# ProProject___2024-05-11.net
KiCad netlist of a schematic drawn in EasyEDA Pro
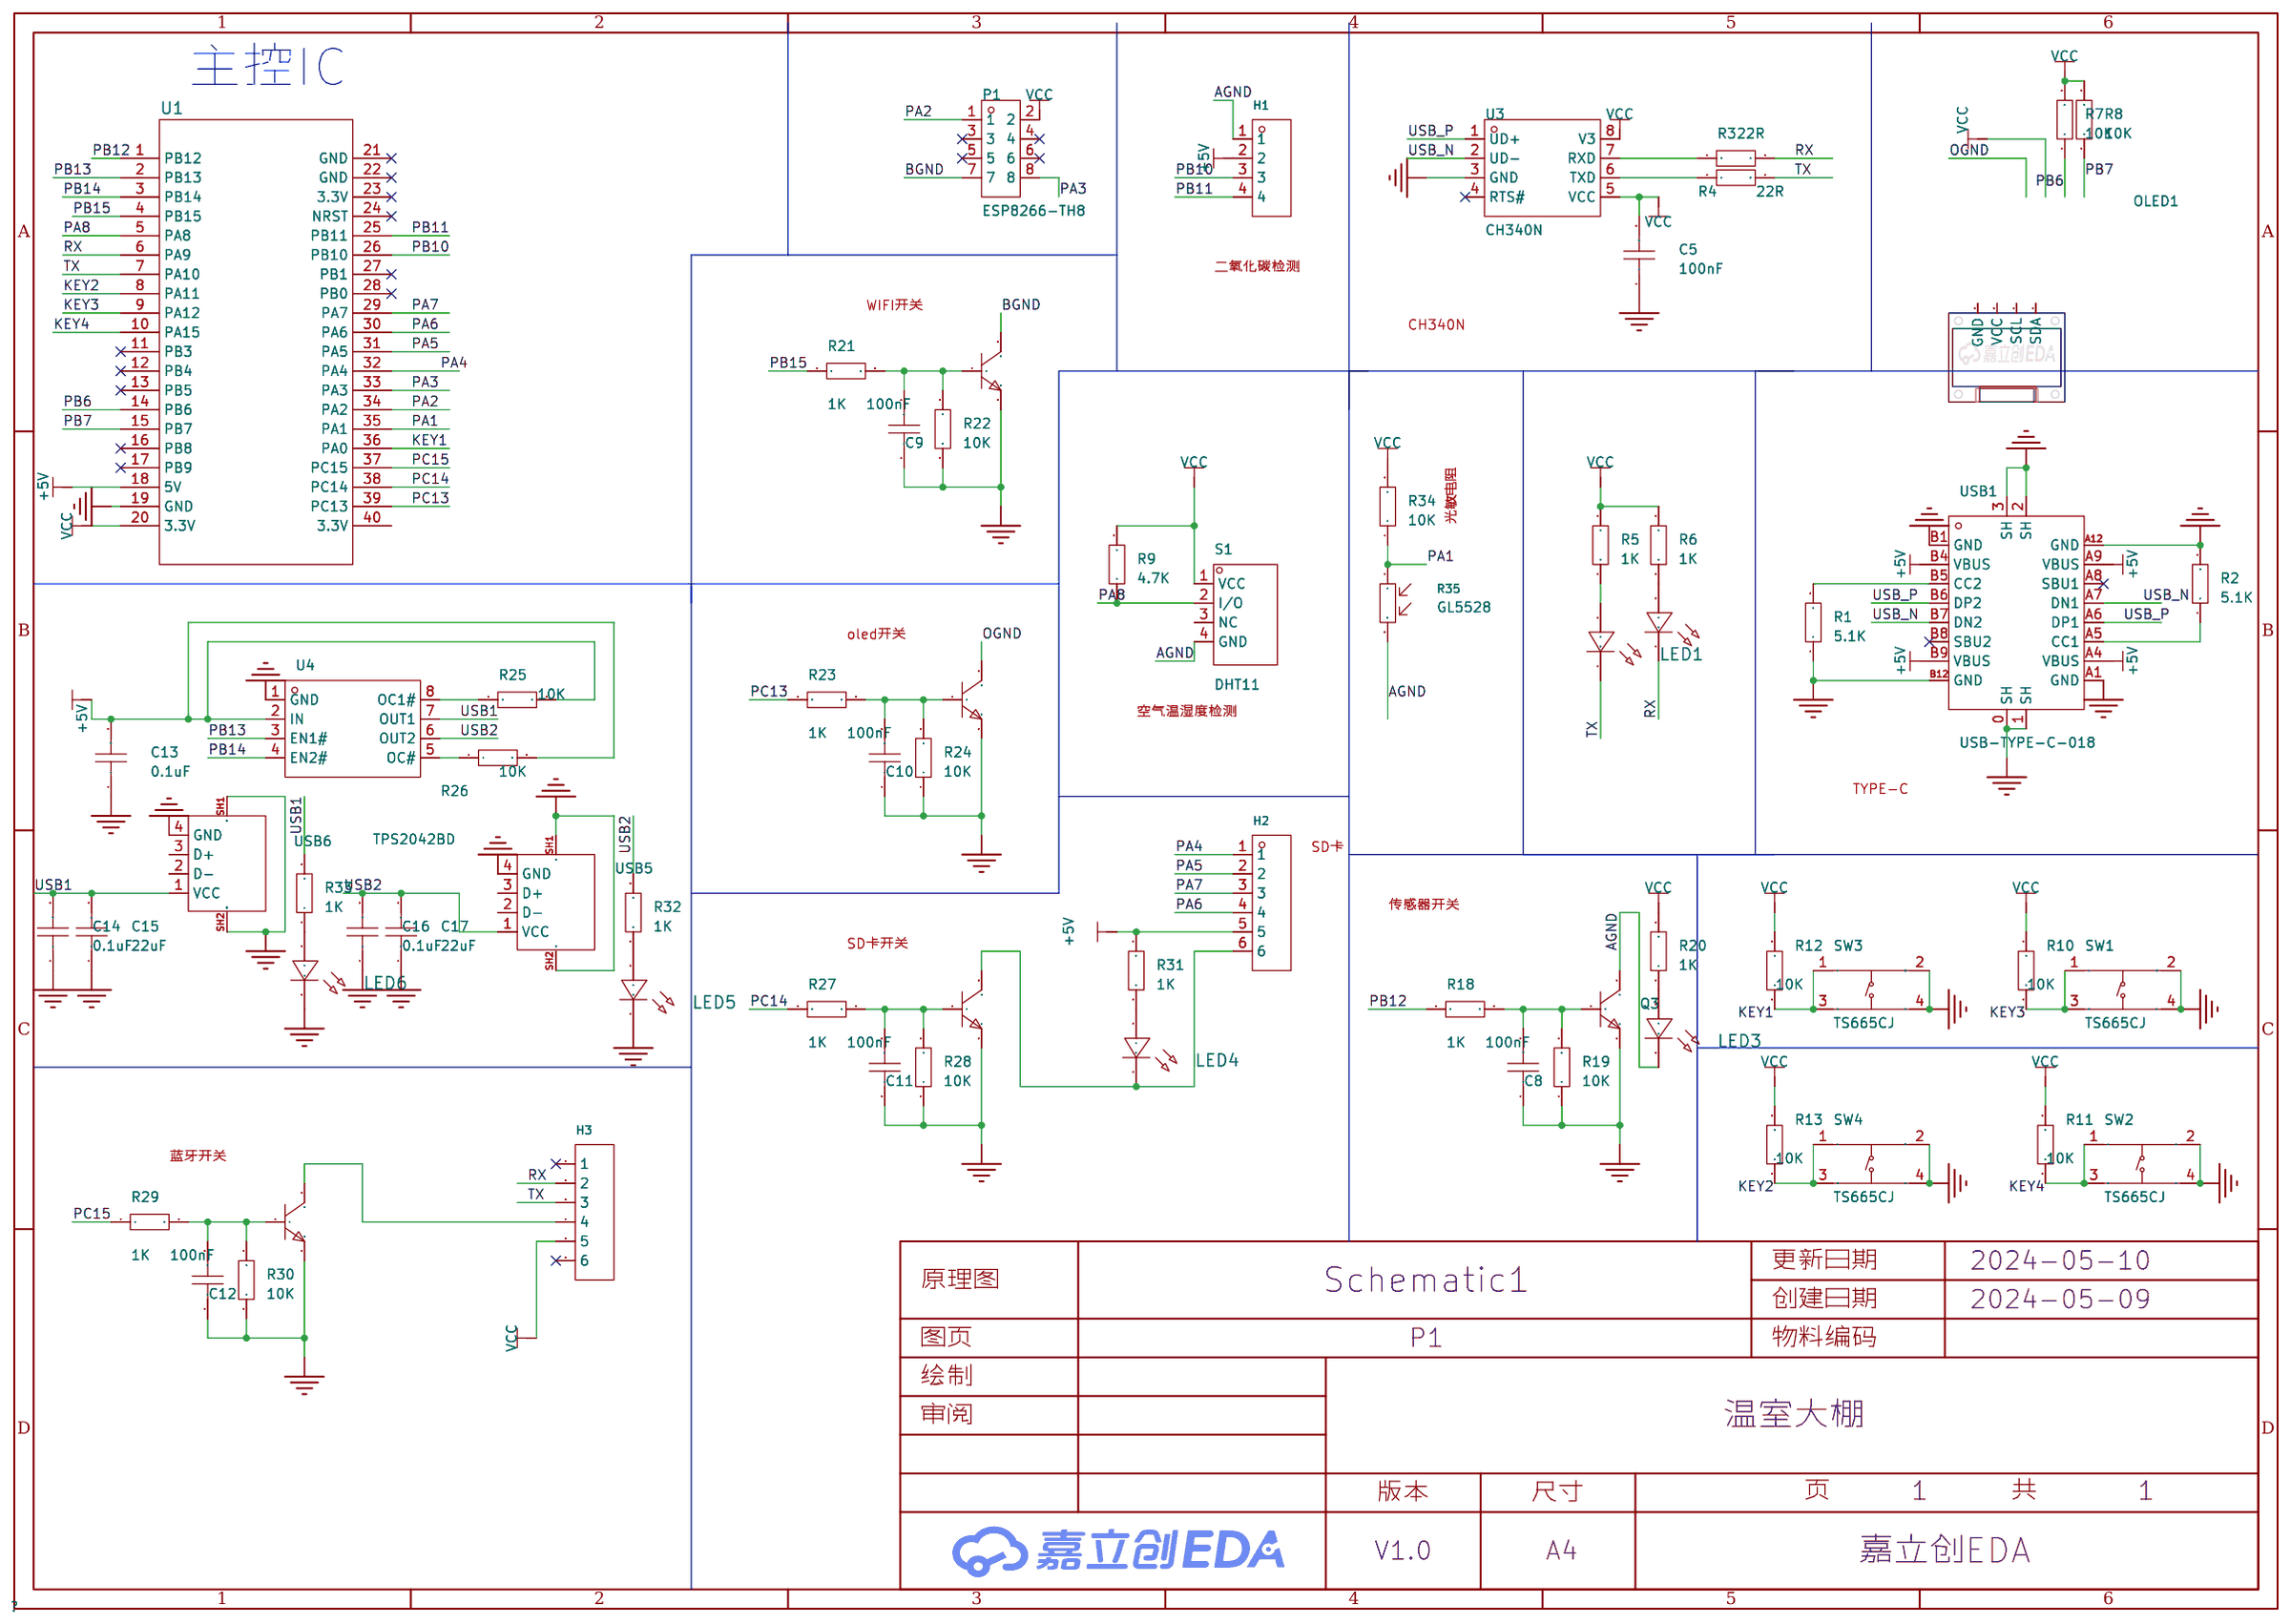
[diagram p0: schematic sheet]

(export (version "E")
  (design (tool "Eeschema 10.0.6"))
  (components
    (comp (ref "C5")
      (value "100nF")
      (footprint "easyedapro:C0603")
      (libsource (lib "easyedapro") (part "CapAcitance"))
    )
    (comp (ref "C8")
      (value "100nF")
      (footprint "easyedapro:C0603")
      (libsource (lib "easyedapro") (part "CapAcitance"))
    )
    (comp (ref "C9")
      (value "100nF")
      (footprint "easyedapro:C0603")
      (libsource (lib "easyedapro") (part "CapAcitance"))
    )
    (comp (ref "C10")
      (value "100nF")
      (footprint "easyedapro:C0603")
      (libsource (lib "easyedapro") (part "CapAcitance"))
    )
    (comp (ref "C11")
      (value "100nF")
      (footprint "easyedapro:C0603")
      (libsource (lib "easyedapro") (part "CapAcitance"))
    )
    (comp (ref "C12")
      (value "100nF")
      (footprint "easyedapro:C0603")
      (libsource (lib "easyedapro") (part "CapAcitance"))
    )
    (comp (ref "C13")
      (value "0.1uF")
      (footprint "easyedapro:C0603")
      (libsource (lib "easyedapro") (part "CapAcitance"))
    )
    (comp (ref "C14")
      (value "0.1uF")
      (footprint "easyedapro:C0603")
      (libsource (lib "easyedapro") (part "CapAcitance"))
    )
    (comp (ref "C15")
      (value "22uF")
      (footprint "easyedapro:C0603")
      (libsource (lib "easyedapro") (part "CapAcitance"))
    )
    (comp (ref "C16")
      (value "0.1uF")
      (footprint "easyedapro:C0603")
      (libsource (lib "easyedapro") (part "CapAcitance"))
    )
    (comp (ref "C17")
      (value "22uF")
      (footprint "easyedapro:C0603")
      (libsource (lib "easyedapro") (part "CapAcitance"))
    )
    (comp (ref "H1")
      (value "~")
      (footprint "easyedapro:HDR-TH_4P-P2.54-V-M")
      (libsource (lib "easyedapro") (part "PZ254V-11-04P"))
    )
    (comp (ref "H2")
      (value "~")
      (footprint "easyedapro:HDR-TH_6P-P2.54-V-F")
      (libsource (lib "easyedapro") (part "Header-Female-2.54_1x6"))
    )
    (comp (ref "H3")
      (value "~")
      (footprint "easyedapro:HDR-TH_6P-P2.54-V-M-1")
      (libsource (lib "easyedapro") (part "Header-Male-2.54_1x6"))
    )
    (comp (ref "LED1")
      (value "~")
      (footprint "easyedapro:LED_0603")
      (libsource (lib "easyedapro") (part "LED_R"))
    )
    (comp (ref "LED2")
      (value "~")
      (footprint "easyedapro:LED_0603")
      (libsource (lib "easyedapro") (part "LED_R"))
    )
    (comp (ref "LED3")
      (value "~")
      (footprint "easyedapro:LED_0603")
      (libsource (lib "easyedapro") (part "LED_R"))
    )
    (comp (ref "LED4")
      (value "~")
      (footprint "easyedapro:LED_0603")
      (libsource (lib "easyedapro") (part "LED_R"))
    )
    (comp (ref "LED5")
      (value "~")
      (footprint "easyedapro:LED_0603")
      (libsource (lib "easyedapro") (part "LED_R"))
    )
    (comp (ref "LED6")
      (value "~")
      (footprint "easyedapro:LED_0603")
      (libsource (lib "easyedapro") (part "LED_R"))
    )
    (comp (ref "OLED1")
      (value "~")
      (footprint "easyedapro:0.96OLED_4P")
      (libsource (lib "easyedapro") (part "0.96OLED模块_4P"))
    )
    (comp (ref "P1")
      (value "ESP8266-TH8")
      (footprint "easyedapro:HDR-TH_8P-P2.54-V-F-R2-C4-S2.54-1")
      (libsource (lib "easyedapro") (part "ESP8266-TH8"))
    )
    (comp (ref "Q3")
      (value "~")
      (footprint "easyedapro:S8050_SOT-23")
      (libsource (lib "easyedapro") (part "NPN"))
    )
    (comp (ref "Q4")
      (value "~")
      (footprint "easyedapro:S8050_SOT-23")
      (libsource (lib "easyedapro") (part "NPN"))
    )
    (comp (ref "Q5")
      (value "~")
      (footprint "easyedapro:S8050_SOT-23")
      (libsource (lib "easyedapro") (part "NPN"))
    )
    (comp (ref "Q6")
      (value "~")
      (footprint "easyedapro:S8050_SOT-23")
      (libsource (lib "easyedapro") (part "NPN"))
    )
    (comp (ref "Q7")
      (value "~")
      (footprint "easyedapro:S8050_SOT-23")
      (libsource (lib "easyedapro") (part "NPN"))
    )
    (comp (ref "R1") (value "5.1K") (footprint "easyedapro:R0603") (libsource (lib "easyedapro") (part "电阻")))
    (comp (ref "R2") (value "5.1K") (footprint "easyedapro:R0603") (libsource (lib "easyedapro") (part "电阻")))
    (comp (ref "R3") (value "22R") (footprint "easyedapro:R0603") (libsource (lib "easyedapro") (part "电阻")))
    (comp (ref "R4") (value "22R") (footprint "easyedapro:R0603") (libsource (lib "easyedapro") (part "电阻")))
    (comp (ref "R5") (value "1K") (footprint "easyedapro:R0603") (libsource (lib "easyedapro") (part "电阻")))
    (comp (ref "R6") (value "1K") (footprint "easyedapro:R0603") (libsource (lib "easyedapro") (part "电阻")))
    (comp (ref "R7") (value "10K") (footprint "easyedapro:R0603") (libsource (lib "easyedapro") (part "电阻")))
    (comp (ref "R8") (value "10K") (footprint "easyedapro:R0603") (libsource (lib "easyedapro") (part "电阻")))
    (comp (ref "R9") (value "4.7K") (footprint "easyedapro:R0603") (libsource (lib "easyedapro") (part "电阻")))
    (comp (ref "R10") (value "10K") (footprint "easyedapro:R0603") (libsource (lib "easyedapro") (part "电阻")))
    (comp (ref "R11") (value "10K") (footprint "easyedapro:R0603") (libsource (lib "easyedapro") (part "电阻")))
    (comp (ref "R12") (value "10K") (footprint "easyedapro:R0603") (libsource (lib "easyedapro") (part "电阻")))
    (comp (ref "R13") (value "10K") (footprint "easyedapro:R0603") (libsource (lib "easyedapro") (part "电阻")))
    (comp (ref "R18") (value "1K") (footprint "easyedapro:R0603") (libsource (lib "easyedapro") (part "电阻")))
    (comp (ref "R19") (value "10K") (footprint "easyedapro:R0603") (libsource (lib "easyedapro") (part "电阻")))
    (comp (ref "R20") (value "1K") (footprint "easyedapro:R0603") (libsource (lib "easyedapro") (part "电阻")))
    (comp (ref "R21") (value "1K") (footprint "easyedapro:R0603") (libsource (lib "easyedapro") (part "电阻")))
    (comp (ref "R22") (value "10K") (footprint "easyedapro:R0603") (libsource (lib "easyedapro") (part "电阻")))
    (comp (ref "R23") (value "1K") (footprint "easyedapro:R0603") (libsource (lib "easyedapro") (part "电阻")))
    (comp (ref "R24") (value "10K") (footprint "easyedapro:R0603") (libsource (lib "easyedapro") (part "电阻")))
    (comp (ref "R25") (value "10K") (footprint "easyedapro:R0603") (libsource (lib "easyedapro") (part "电阻")))
    (comp (ref "R26") (value "10K") (footprint "easyedapro:R0603") (libsource (lib "easyedapro") (part "电阻")))
    (comp (ref "R27") (value "1K") (footprint "easyedapro:R0603") (libsource (lib "easyedapro") (part "电阻")))
    (comp (ref "R28") (value "10K") (footprint "easyedapro:R0603") (libsource (lib "easyedapro") (part "电阻")))
    (comp (ref "R29") (value "1K") (footprint "easyedapro:R0603") (libsource (lib "easyedapro") (part "电阻")))
    (comp (ref "R30") (value "10K") (footprint "easyedapro:R0603") (libsource (lib "easyedapro") (part "电阻")))
    (comp (ref "R31") (value "1K") (footprint "easyedapro:R0603") (libsource (lib "easyedapro") (part "电阻")))
    (comp (ref "R32") (value "1K") (footprint "easyedapro:R0603") (libsource (lib "easyedapro") (part "电阻")))
    (comp (ref "R33") (value "1K") (footprint "easyedapro:R0603") (libsource (lib "easyedapro") (part "电阻")))
    (comp (ref "R34") (value "10K") (footprint "easyedapro:R0603") (libsource (lib "easyedapro") (part "电阻")))
    (comp (ref "R35")
      (value "GL5528")
      (footprint "easyedapro:RES-TH_L5.1-W4.3-P3.40-D0.5")
      (description "暗电阻:1MΩ;亮电阻 @ 10Lux:8kΩ~20kΩ;光谱峰值(波长):540nm;")
      (fields (field (name "Manufacturer") "森霸"))
      (libsource (lib "easyedapro") (part "GL5528"))
    )
    (comp (ref "S1")
      (value "DHT11")
      (footprint "easyedapro:SENSOR-TH_DHT11-1")
      (description "温湿度模块，数字式，单总线")
      (libsource (lib "easyedapro") (part "DHT11_C87032"))
    )
    (comp (ref "SW1")
      (value "TS665CJ")
      (footprint "easyedapro:SW-TH_4P-L6.0-W6.0-P4.50-LS6.5")
      (description "电路结构:单刀单掷;按钮形状:圆形按钮;安装方式:直插;开关长度:6mm;开关宽度:6mm;开关高度:5mm;触点电流:50mA;额定电压(DC):12V;带灯:-;机械寿命:-;")
      (fields (field (name "Manufacturer") "SHOU HAN(首韩)"))
      (libsource (lib "easyedapro") (part "TS665CJ"))
    )
    (comp (ref "SW2")
      (value "TS665CJ")
      (footprint "easyedapro:SW-TH_4P-L6.0-W6.0-P4.50-LS6.5")
      (description "电路结构:单刀单掷;按钮形状:圆形按钮;安装方式:直插;开关长度:6mm;开关宽度:6mm;开关高度:5mm;触点电流:50mA;额定电压(DC):12V;带灯:-;机械寿命:-;")
      (fields (field (name "Manufacturer") "SHOU HAN(首韩)"))
      (libsource (lib "easyedapro") (part "TS665CJ"))
    )
    (comp (ref "SW3")
      (value "TS665CJ")
      (footprint "easyedapro:SW-TH_4P-L6.0-W6.0-P4.50-LS6.5")
      (description "电路结构:单刀单掷;按钮形状:圆形按钮;安装方式:直插;开关长度:6mm;开关宽度:6mm;开关高度:5mm;触点电流:50mA;额定电压(DC):12V;带灯:-;机械寿命:-;")
      (fields (field (name "Manufacturer") "SHOU HAN(首韩)"))
      (libsource (lib "easyedapro") (part "TS665CJ"))
    )
    (comp (ref "SW4")
      (value "TS665CJ")
      (footprint "easyedapro:SW-TH_4P-L6.0-W6.0-P4.50-LS6.5")
      (description "电路结构:单刀单掷;按钮形状:圆形按钮;安装方式:直插;开关长度:6mm;开关宽度:6mm;开关高度:5mm;触点电流:50mA;额定电压(DC):12V;带灯:-;机械寿命:-;")
      (fields (field (name "Manufacturer") "SHOU HAN(首韩)"))
      (libsource (lib "easyedapro") (part "TS665CJ"))
    )
    (comp (ref "U1")
      (value "STM32F103C8T6最小系统")
      (footprint "easyedapro:STM32F103C8T6")
      (libsource (lib "easyedapro") (part "STM32F103C8T6最小系统_1"))
    )
    (comp (ref "U3")
      (value "CH340N")
      (footprint "easyedapro:SOP-8_L4.9-W3.9-P1.27-LS6.0-BL")
      (fields (field (name "Manufacturer") "WCH(南京沁恒)"))
      (libsource (lib "easyedapro") (part "CH340N_C2977777"))
    )
    (comp (ref "U4")
      (value "TPS2042BD")
      (footprint "easyedapro:SOIC-8_L5.0-W4.0-P1.27-LS6.1-BL")
      (description "通道数:2;输出电流:500mA;输入电压:2.7V~5.5V;导通电阻:70mΩ;")
      (fields (field (name "Manufacturer") "TI(德州仪器)"))
      (libsource (lib "easyedapro") (part "TPS2042BD"))
    )
    (comp (ref "USB1")
      (value "USB-TYPE-C-018")
      (footprint "easyedapro:USB-C_SMD-TYPE-C-31-M-12")
      (description "连接器类型:Type-C;标准:-;公母:母;端口数量:1;触点数量:16P;安装方式:卧贴;额定电流 - 电源:3A;工作温度范围:-25°C~+85°C;")
      (fields (field (name "Manufacturer") "DEALON(德艺隆)"))
      (libsource (lib "easyedapro") (part "USB-TYPE-C-018"))
    )
    (comp (ref "USB5")
      (value "~")
      (footprint "easyedapro:USB_ Type-A")
      (libsource (lib "easyedapro") (part "USB_Type-A"))
    )
    (comp (ref "USB6")
      (value "~")
      (footprint "easyedapro:USB_ Type-A")
      (libsource (lib "easyedapro") (part "USB_Type-A"))
    )
  )
  (nets
    (net (code "1") (name "+5V") (class "Default")
      (node (ref "C13") (pin "2") (pinfunction "2_2") (pintype "input"))
      (node (ref "H1") (pin "2") (pinfunction "2_2") (pintype "input"))
      (node (ref "H2") (pin "5") (pinfunction "5_5") (pintype "input"))
      (node (ref "R25") (pin "2") (pinfunction "2_2") (pintype "input"))
      (node (ref "R26") (pin "2") (pinfunction "2_2") (pintype "input"))
      (node (ref "R31") (pin "2") (pinfunction "2_2") (pintype "input"))
      (node (ref "U1") (pin "18") (pinfunction "5V_18") (pintype "input"))
      (node (ref "U4") (pin "2") (pinfunction "IN_2") (pintype "input"))
      (node (ref "USB1") (pin "A4") (pinfunction "VBUS_A4") (pintype "unspecified"))
      (node (ref "USB1") (pin "A9") (pinfunction "VBUS_A9") (pintype "unspecified"))
      (node (ref "USB1") (pin "B4") (pinfunction "VBUS_B4") (pintype "unspecified"))
      (node (ref "USB1") (pin "B9") (pinfunction "VBUS_B9") (pintype "unspecified"))
    )
    (net (code "2") (name "/AGND") (class "Default")
      (node (ref "H1") (pin "1") (pinfunction "1_1") (pintype "input"))
      (node (ref "LED3") (pin "1") (pinfunction "C_1") (pintype "input"))
      (node (ref "Q3") (pin "3") (pinfunction "3_3") (pintype "unspecified"))
      (node (ref "R35") (pin "2") (pinfunction "2_2") (pintype "input"))
      (node (ref "S1") (pin "4") (pinfunction "GND_4") (pintype "unspecified"))
    )
    (net (code "3") (name "/BGND") (class "Default")
      (node (ref "P1") (pin "7") (pinfunction "7_7") (pintype "unspecified"))
      (node (ref "Q4") (pin "3") (pinfunction "3_3") (pintype "unspecified"))
    )
    (net (code "4") (name "/KEY1") (class "Default")
      (node (ref "R12") (pin "1") (pinfunction "1_1") (pintype "input"))
      (node (ref "SW3") (pin "1") (pinfunction "A_1") (pintype "unspecified"))
      (node (ref "SW3") (pin "3") (pinfunction "C_3") (pintype "unspecified"))
      (node (ref "U1") (pin "36") (pinfunction "PA0_36") (pintype "bidirectional"))
    )
    (net (code "5") (name "/KEY2") (class "Default")
      (node (ref "R13") (pin "1") (pinfunction "1_1") (pintype "input"))
      (node (ref "SW4") (pin "1") (pinfunction "A_1") (pintype "unspecified"))
      (node (ref "SW4") (pin "3") (pinfunction "C_3") (pintype "unspecified"))
      (node (ref "U1") (pin "8") (pinfunction "PA11_8") (pintype "bidirectional"))
    )
    (net (code "6") (name "/KEY3") (class "Default")
      (node (ref "R10") (pin "1") (pinfunction "1_1") (pintype "input"))
      (node (ref "SW1") (pin "1") (pinfunction "A_1") (pintype "unspecified"))
      (node (ref "SW1") (pin "3") (pinfunction "C_3") (pintype "unspecified"))
      (node (ref "U1") (pin "9") (pinfunction "PA12_9") (pintype "bidirectional"))
    )
    (net (code "7") (name "/KEY4") (class "Default")
      (node (ref "R11") (pin "1") (pinfunction "1_1") (pintype "input"))
      (node (ref "SW2") (pin "1") (pinfunction "A_1") (pintype "unspecified"))
      (node (ref "SW2") (pin "3") (pinfunction "C_3") (pintype "unspecified"))
      (node (ref "U1") (pin "10") (pinfunction "PA15_10") (pintype "bidirectional"))
    )
    (net (code "8") (name "/OGND") (class "Default")
      (node (ref "Q5") (pin "3") (pinfunction "3_3") (pintype "unspecified"))
    )
    (net (code "9") (name "/PA1") (class "Default")
      (node (ref "R34") (pin "1") (pinfunction "1_1") (pintype "input"))
      (node (ref "R35") (pin "1") (pinfunction "1_1") (pintype "input"))
      (node (ref "U1") (pin "35") (pinfunction "PA1_35") (pintype "bidirectional"))
    )
    (net (code "10") (name "/PA2") (class "Default")
      (node (ref "P1") (pin "1") (pinfunction "1_1") (pintype "unspecified"))
      (node (ref "U1") (pin "34") (pinfunction "PA2_34") (pintype "bidirectional"))
    )
    (net (code "11") (name "/PA3") (class "Default")
      (node (ref "P1") (pin "8") (pinfunction "8_8") (pintype "unspecified"))
      (node (ref "U1") (pin "33") (pinfunction "PA3_33") (pintype "bidirectional"))
    )
    (net (code "12") (name "/PA4") (class "Default")
      (node (ref "H2") (pin "1") (pinfunction "1_1") (pintype "input"))
      (node (ref "U1") (pin "32") (pinfunction "PA4_32") (pintype "bidirectional"))
    )
    (net (code "13") (name "/PA5") (class "Default")
      (node (ref "H2") (pin "2") (pinfunction "2_2") (pintype "input"))
      (node (ref "U1") (pin "31") (pinfunction "PA5_31") (pintype "bidirectional"))
    )
    (net (code "14") (name "/PA6") (class "Default")
      (node (ref "H2") (pin "4") (pinfunction "4_4") (pintype "input"))
      (node (ref "U1") (pin "30") (pinfunction "PA6_30") (pintype "bidirectional"))
    )
    (net (code "15") (name "/PA7") (class "Default")
      (node (ref "H2") (pin "3") (pinfunction "3_3") (pintype "input"))
      (node (ref "U1") (pin "29") (pinfunction "PA7_29") (pintype "bidirectional"))
    )
    (net (code "16") (name "/PA8") (class "Default")
      (node (ref "R9") (pin "1") (pinfunction "1_1") (pintype "input"))
      (node (ref "S1") (pin "2") (pinfunction "I/O_2") (pintype "unspecified"))
      (node (ref "U1") (pin "5") (pinfunction "PA8_5") (pintype "bidirectional"))
    )
    (net (code "17") (name "/PB6") (class "Default")
      (node (ref "R7") (pin "1") (pinfunction "1_1") (pintype "input"))
      (node (ref "U1") (pin "14") (pinfunction "PB6_14") (pintype "bidirectional"))
    )
    (net (code "18") (name "/PB7") (class "Default")
      (node (ref "R8") (pin "1") (pinfunction "1_1") (pintype "input"))
      (node (ref "U1") (pin "15") (pinfunction "PB7_15") (pintype "bidirectional"))
    )
    (net (code "19") (name "/PB10") (class "Default")
      (node (ref "H1") (pin "3") (pinfunction "3_3") (pintype "input"))
      (node (ref "U1") (pin "26") (pinfunction "PB10_26") (pintype "bidirectional"))
    )
    (net (code "20") (name "/PB11") (class "Default")
      (node (ref "H1") (pin "4") (pinfunction "4_4") (pintype "input"))
      (node (ref "U1") (pin "25") (pinfunction "PB11_25") (pintype "bidirectional"))
    )
    (net (code "21") (name "/PB12") (class "Default")
      (node (ref "R18") (pin "1") (pinfunction "1_1") (pintype "input"))
      (node (ref "U1") (pin "1") (pinfunction "PB12_1") (pintype "bidirectional"))
    )
    (net (code "22") (name "/PB13") (class "Default")
      (node (ref "U1") (pin "2") (pinfunction "PB13_2") (pintype "bidirectional"))
      (node (ref "U4") (pin "3") (pinfunction "EN1#_3") (pintype "input"))
    )
    (net (code "23") (name "/PB14") (class "Default")
      (node (ref "U1") (pin "3") (pinfunction "PB14_3") (pintype "bidirectional"))
      (node (ref "U4") (pin "4") (pinfunction "EN2#_4") (pintype "input"))
    )
    (net (code "24") (name "/PB15") (class "Default")
      (node (ref "R21") (pin "1") (pinfunction "1_1") (pintype "input"))
      (node (ref "U1") (pin "4") (pinfunction "PB15_4") (pintype "bidirectional"))
    )
    (net (code "25") (name "/PC13") (class "Default")
      (node (ref "R23") (pin "1") (pinfunction "1_1") (pintype "input"))
      (node (ref "U1") (pin "39") (pinfunction "PC13_39") (pintype "bidirectional"))
    )
    (net (code "26") (name "/PC14") (class "Default")
      (node (ref "R27") (pin "1") (pinfunction "1_1") (pintype "input"))
      (node (ref "U1") (pin "38") (pinfunction "PC14_38") (pintype "bidirectional"))
    )
    (net (code "27") (name "/PC15") (class "Default")
      (node (ref "R29") (pin "1") (pinfunction "1_1") (pintype "input"))
      (node (ref "U1") (pin "37") (pinfunction "PC15_37") (pintype "bidirectional"))
    )
    (net (code "28") (name "/RX") (class "Default")
      (node (ref "H3") (pin "2") (pinfunction "2_2") (pintype "input"))
      (node (ref "LED2") (pin "1") (pinfunction "C_1") (pintype "input"))
      (node (ref "R3") (pin "2") (pinfunction "2_2") (pintype "input"))
      (node (ref "U1") (pin "6") (pinfunction "PA9_6") (pintype "bidirectional"))
    )
    (net (code "29") (name "/TX") (class "Default")
      (node (ref "H3") (pin "3") (pinfunction "3_3") (pintype "input"))
      (node (ref "LED1") (pin "1") (pinfunction "C_1") (pintype "input"))
      (node (ref "R4") (pin "2") (pinfunction "2_2") (pintype "input"))
      (node (ref "U1") (pin "7") (pinfunction "PA10_7") (pintype "bidirectional"))
    )
    (net (code "30") (name "/USB1") (class "Default")
      (node (ref "C14") (pin "2") (pinfunction "2_2") (pintype "input"))
      (node (ref "C15") (pin "2") (pinfunction "2_2") (pintype "input"))
      (node (ref "R33") (pin "2") (pinfunction "2_2") (pintype "input"))
      (node (ref "U4") (pin "7") (pinfunction "OUT1_7") (pintype "input"))
      (node (ref "USB6") (pin "1") (pinfunction "VCC_1") (pintype "input"))
    )
    (net (code "31") (name "/USB2") (class "Default")
      (node (ref "C16") (pin "2") (pinfunction "2_2") (pintype "input"))
      (node (ref "C17") (pin "2") (pinfunction "2_2") (pintype "input"))
      (node (ref "R32") (pin "2") (pinfunction "2_2") (pintype "input"))
      (node (ref "U4") (pin "6") (pinfunction "OUT2_6") (pintype "input"))
      (node (ref "USB5") (pin "1") (pinfunction "VCC_1") (pintype "input"))
    )
    (net (code "32") (name "/USB_N") (class "Default")
      (node (ref "U3") (pin "2") (pinfunction "UD-_2") (pintype "unspecified"))
      (node (ref "USB1") (pin "A7") (pinfunction "DN1_A7") (pintype "unspecified"))
      (node (ref "USB1") (pin "B7") (pinfunction "DN2_B7") (pintype "unspecified"))
    )
    (net (code "33") (name "/USB_P") (class "Default")
      (node (ref "U3") (pin "1") (pinfunction "UD+_1") (pintype "unspecified"))
      (node (ref "USB1") (pin "A6") (pinfunction "DP1_A6") (pintype "unspecified"))
      (node (ref "USB1") (pin "B6") (pinfunction "DP2_B6") (pintype "unspecified"))
    )
    (net (code "34") (name "GND") (class "Default")
      (node (ref "C10") (pin "1") (pinfunction "1_1") (pintype "input"))
      (node (ref "C11") (pin "1") (pinfunction "1_1") (pintype "input"))
      (node (ref "C12") (pin "1") (pinfunction "1_1") (pintype "input"))
      (node (ref "C13") (pin "1") (pinfunction "1_1") (pintype "input"))
      (node (ref "C14") (pin "1") (pinfunction "1_1") (pintype "input"))
      (node (ref "C15") (pin "1") (pinfunction "1_1") (pintype "input"))
      (node (ref "C16") (pin "1") (pinfunction "1_1") (pintype "input"))
      (node (ref "C17") (pin "1") (pinfunction "1_1") (pintype "input"))
      (node (ref "C5") (pin "1") (pinfunction "1_1") (pintype "input"))
      (node (ref "C8") (pin "1") (pinfunction "1_1") (pintype "input"))
      (node (ref "C9") (pin "1") (pinfunction "1_1") (pintype "input"))
      (node (ref "LED5") (pin "1") (pinfunction "C_1") (pintype "input"))
      (node (ref "LED6") (pin "1") (pinfunction "C_1") (pintype "input"))
      (node (ref "Q3") (pin "2") (pinfunction "2_2") (pintype "unspecified"))
      (node (ref "Q4") (pin "2") (pinfunction "2_2") (pintype "unspecified"))
      (node (ref "Q5") (pin "2") (pinfunction "2_2") (pintype "unspecified"))
      (node (ref "Q6") (pin "2") (pinfunction "2_2") (pintype "unspecified"))
      (node (ref "Q7") (pin "2") (pinfunction "2_2") (pintype "unspecified"))
      (node (ref "R1") (pin "1") (pinfunction "1_1") (pintype "input"))
      (node (ref "R19") (pin "1") (pinfunction "1_1") (pintype "input"))
      (node (ref "R2") (pin "2") (pinfunction "2_2") (pintype "input"))
      (node (ref "R22") (pin "1") (pinfunction "1_1") (pintype "input"))
      (node (ref "R24") (pin "1") (pinfunction "1_1") (pintype "input"))
      (node (ref "R28") (pin "1") (pinfunction "1_1") (pintype "input"))
      (node (ref "R30") (pin "1") (pinfunction "1_1") (pintype "input"))
      (node (ref "SW1") (pin "2") (pinfunction "B_2") (pintype "unspecified"))
      (node (ref "SW1") (pin "4") (pinfunction "D_4") (pintype "unspecified"))
      (node (ref "SW2") (pin "2") (pinfunction "B_2") (pintype "unspecified"))
      (node (ref "SW2") (pin "4") (pinfunction "D_4") (pintype "unspecified"))
      (node (ref "SW3") (pin "2") (pinfunction "B_2") (pintype "unspecified"))
      (node (ref "SW3") (pin "4") (pinfunction "D_4") (pintype "unspecified"))
      (node (ref "SW4") (pin "2") (pinfunction "B_2") (pintype "unspecified"))
      (node (ref "SW4") (pin "4") (pinfunction "D_4") (pintype "unspecified"))
      (node (ref "U1") (pin "19") (pinfunction "GND_19") (pintype "input"))
      (node (ref "U3") (pin "3") (pinfunction "GND_3") (pintype "unspecified"))
      (node (ref "U4") (pin "1") (pinfunction "GND_1") (pintype "input"))
      (node (ref "USB1") (pin "0") (pinfunction "SH_0") (pintype "unspecified"))
      (node (ref "USB1") (pin "1") (pinfunction "SH_1") (pintype "unspecified"))
      (node (ref "USB1") (pin "2") (pinfunction "SH_2") (pintype "unspecified"))
      (node (ref "USB1") (pin "3") (pinfunction "SH_3") (pintype "unspecified"))
      (node (ref "USB1") (pin "A1") (pinfunction "GND_A1") (pintype "unspecified"))
      (node (ref "USB1") (pin "A12") (pinfunction "GND_A12") (pintype "unspecified"))
      (node (ref "USB1") (pin "B1") (pinfunction "GND_B1") (pintype "unspecified"))
      (node (ref "USB1") (pin "B12") (pinfunction "GND_B12") (pintype "unspecified"))
      (node (ref "USB5") (pin "4") (pinfunction "GND_4") (pintype "input"))
      (node (ref "USB5") (pin "SH1") (pinfunction "SH1_SH1") (pintype "input"))
      (node (ref "USB5") (pin "SH2") (pinfunction "SH2_SH2") (pintype "input"))
      (node (ref "USB6") (pin "4") (pinfunction "GND_4") (pintype "input"))
      (node (ref "USB6") (pin "SH1") (pinfunction "SH1_SH1") (pintype "input"))
      (node (ref "USB6") (pin "SH2") (pinfunction "SH2_SH2") (pintype "input"))
    )
    (net (code "35") (name "Net-(C8-Pad2)") (class "Default")
      (node (ref "C8") (pin "2") (pinfunction "2_2") (pintype "input"))
      (node (ref "Q3") (pin "1") (pinfunction "1_1") (pintype "unspecified"))
      (node (ref "R18") (pin "2") (pinfunction "2_2") (pintype "input"))
      (node (ref "R19") (pin "2") (pinfunction "2_2") (pintype "input"))
    )
    (net (code "36") (name "Net-(C9-Pad2)") (class "Default")
      (node (ref "C9") (pin "2") (pinfunction "2_2") (pintype "input"))
      (node (ref "Q4") (pin "1") (pinfunction "1_1") (pintype "unspecified"))
      (node (ref "R21") (pin "2") (pinfunction "2_2") (pintype "input"))
      (node (ref "R22") (pin "2") (pinfunction "2_2") (pintype "input"))
    )
    (net (code "37") (name "Net-(C10-Pad2)") (class "Default")
      (node (ref "C10") (pin "2") (pinfunction "2_2") (pintype "input"))
      (node (ref "Q5") (pin "1") (pinfunction "1_1") (pintype "unspecified"))
      (node (ref "R23") (pin "2") (pinfunction "2_2") (pintype "input"))
      (node (ref "R24") (pin "2") (pinfunction "2_2") (pintype "input"))
    )
    (net (code "38") (name "Net-(C11-Pad2)") (class "Default")
      (node (ref "C11") (pin "2") (pinfunction "2_2") (pintype "input"))
      (node (ref "Q6") (pin "1") (pinfunction "1_1") (pintype "unspecified"))
      (node (ref "R27") (pin "2") (pinfunction "2_2") (pintype "input"))
      (node (ref "R28") (pin "2") (pinfunction "2_2") (pintype "input"))
    )
    (net (code "39") (name "Net-(C12-Pad2)") (class "Default")
      (node (ref "C12") (pin "2") (pinfunction "2_2") (pintype "input"))
      (node (ref "Q7") (pin "1") (pinfunction "1_1") (pintype "unspecified"))
      (node (ref "R29") (pin "2") (pinfunction "2_2") (pintype "input"))
      (node (ref "R30") (pin "2") (pinfunction "2_2") (pintype "input"))
    )
    (net (code "40") (name "Net-(H3-Pad4)") (class "Default")
      (node (ref "H3") (pin "4") (pinfunction "4_4") (pintype "input"))
      (node (ref "Q7") (pin "3") (pinfunction "3_3") (pintype "unspecified"))
    )
    (net (code "41") (name "Net-(LED1-A)") (class "Default")
      (node (ref "LED1") (pin "2") (pinfunction "A_2") (pintype "input"))
      (node (ref "R5") (pin "1") (pinfunction "1_1") (pintype "input"))
    )
    (net (code "42") (name "Net-(LED2-A)") (class "Default")
      (node (ref "LED2") (pin "2") (pinfunction "A_2") (pintype "input"))
      (node (ref "R6") (pin "1") (pinfunction "1_1") (pintype "input"))
    )
    (net (code "43") (name "Net-(LED3-A)") (class "Default")
      (node (ref "LED3") (pin "2") (pinfunction "A_2") (pintype "input"))
      (node (ref "R20") (pin "1") (pinfunction "1_1") (pintype "input"))
    )
    (net (code "44") (name "Net-(LED4-A)") (class "Default")
      (node (ref "LED4") (pin "2") (pinfunction "A_2") (pintype "input"))
      (node (ref "R31") (pin "1") (pinfunction "1_1") (pintype "input"))
    )
    (net (code "45") (name "Net-(LED4-C)") (class "Default")
      (node (ref "H2") (pin "6") (pinfunction "6_6") (pintype "input"))
      (node (ref "LED4") (pin "1") (pinfunction "C_1") (pintype "input"))
      (node (ref "Q6") (pin "3") (pinfunction "3_3") (pintype "unspecified"))
    )
    (net (code "46") (name "Net-(LED5-A)") (class "Default")
      (node (ref "LED5") (pin "2") (pinfunction "A_2") (pintype "input"))
      (node (ref "R32") (pin "1") (pinfunction "1_1") (pintype "input"))
    )
    (net (code "47") (name "Net-(LED6-A)") (class "Default")
      (node (ref "LED6") (pin "2") (pinfunction "A_2") (pintype "input"))
      (node (ref "R33") (pin "1") (pinfunction "1_1") (pintype "input"))
    )
    (net (code "48") (name "Net-(U3-RXD)") (class "Default")
      (node (ref "R3") (pin "1") (pinfunction "1_1") (pintype "input"))
      (node (ref "U3") (pin "7") (pinfunction "RXD_7") (pintype "unspecified"))
    )
    (net (code "49") (name "Net-(U3-TXD)") (class "Default")
      (node (ref "R4") (pin "1") (pinfunction "1_1") (pintype "input"))
      (node (ref "U3") (pin "6") (pinfunction "TXD_6") (pintype "unspecified"))
    )
    (net (code "50") (name "Net-(U4-OC#)") (class "Default")
      (node (ref "R26") (pin "1") (pinfunction "1_1") (pintype "input"))
      (node (ref "U4") (pin "5") (pinfunction "OC#_5") (pintype "input"))
    )
    (net (code "51") (name "Net-(U4-OC1#)") (class "Default")
      (node (ref "R25") (pin "1") (pinfunction "1_1") (pintype "input"))
      (node (ref "U4") (pin "8") (pinfunction "OC1#_8") (pintype "input"))
    )
    (net (code "52") (name "Net-(USB1-CC1)") (class "Default")
      (node (ref "R2") (pin "1") (pinfunction "1_1") (pintype "input"))
      (node (ref "USB1") (pin "A5") (pinfunction "CC1_A5") (pintype "unspecified"))
    )
    (net (code "53") (name "Net-(USB1-CC2)") (class "Default")
      (node (ref "R1") (pin "2") (pinfunction "2_2") (pintype "input"))
      (node (ref "USB1") (pin "B5") (pinfunction "CC2_B5") (pintype "unspecified"))
    )
    (net (code "54") (name "VCC") (class "Default")
      (node (ref "C5") (pin "2") (pinfunction "2_2") (pintype "input"))
      (node (ref "H3") (pin "5") (pinfunction "5_5") (pintype "input"))
      (node (ref "P1") (pin "2") (pinfunction "2_2") (pintype "unspecified"))
      (node (ref "R10") (pin "2") (pinfunction "2_2") (pintype "input"))
      (node (ref "R11") (pin "2") (pinfunction "2_2") (pintype "input"))
      (node (ref "R12") (pin "2") (pinfunction "2_2") (pintype "input"))
      (node (ref "R13") (pin "2") (pinfunction "2_2") (pintype "input"))
      (node (ref "R20") (pin "2") (pinfunction "2_2") (pintype "input"))
      (node (ref "R34") (pin "2") (pinfunction "2_2") (pintype "input"))
      (node (ref "R5") (pin "2") (pinfunction "2_2") (pintype "input"))
      (node (ref "R6") (pin "2") (pinfunction "2_2") (pintype "input"))
      (node (ref "R7") (pin "2") (pinfunction "2_2") (pintype "input"))
      (node (ref "R8") (pin "2") (pinfunction "2_2") (pintype "input"))
      (node (ref "R9") (pin "2") (pinfunction "2_2") (pintype "input"))
      (node (ref "S1") (pin "1") (pinfunction "VCC_1") (pintype "unspecified"))
      (node (ref "U1") (pin "20") (pinfunction "3.3V_20") (pintype "input"))
      (node (ref "U3") (pin "5") (pinfunction "VCC_5") (pintype "unspecified"))
      (node (ref "U3") (pin "8") (pinfunction "V3_8") (pintype "unspecified"))
    )
    (net (code "55") (name "unconnected-(H3-Pad1)") (class "Default")
      (node (ref "H3") (pin "1") (pinfunction "1_1") (pintype "input+no_connect"))
    )
    (net (code "56") (name "unconnected-(H3-Pad6)") (class "Default")
      (node (ref "H3") (pin "6") (pinfunction "6_6") (pintype "input+no_connect"))
    )
    (net (code "57") (name "unconnected-(OLED1-GND-Pad1)") (class "Default")
      (node (ref "OLED1") (pin "1") (pinfunction "GND_1") (pintype "input"))
    )
    (net (code "58") (name "unconnected-(OLED1-SCL-Pad3)") (class "Default")
      (node (ref "OLED1") (pin "3") (pinfunction "SCL_3") (pintype "input"))
    )
    (net (code "59") (name "unconnected-(OLED1-SDA-Pad4)") (class "Default")
      (node (ref "OLED1") (pin "4") (pinfunction "SDA_4") (pintype "input"))
    )
    (net (code "60") (name "unconnected-(OLED1-VCC-Pad2)") (class "Default")
      (node (ref "OLED1") (pin "2") (pinfunction "VCC_2") (pintype "input"))
    )
    (net (code "61") (name "unconnected-(P1-Pad3)") (class "Default")
      (node (ref "P1") (pin "3") (pinfunction "3_3") (pintype "unspecified+no_connect"))
    )
    (net (code "62") (name "unconnected-(P1-Pad4)") (class "Default")
      (node (ref "P1") (pin "4") (pinfunction "4_4") (pintype "unspecified+no_connect"))
    )
    (net (code "63") (name "unconnected-(P1-Pad5)") (class "Default")
      (node (ref "P1") (pin "5") (pinfunction "5_5") (pintype "unspecified+no_connect"))
    )
    (net (code "64") (name "unconnected-(P1-Pad6)") (class "Default")
      (node (ref "P1") (pin "6") (pinfunction "6_6") (pintype "unspecified+no_connect"))
    )
    (net (code "65") (name "unconnected-(S1-NC-Pad3)") (class "Default")
      (node (ref "S1") (pin "3") (pinfunction "NC_3") (pintype "unspecified"))
    )
    (net (code "66") (name "unconnected-(U1-3.3V-Pad23)") (class "Default")
      (node (ref "U1") (pin "23") (pinfunction "3.3V_23") (pintype "input+no_connect"))
    )
    (net (code "67") (name "unconnected-(U1-3.3V-Pad40)") (class "Default")
      (node (ref "U1") (pin "40") (pinfunction "3.3V_40") (pintype "input"))
    )
    (net (code "68") (name "unconnected-(U1-GND-Pad21)") (class "Default")
      (node (ref "U1") (pin "21") (pinfunction "GND_21") (pintype "input+no_connect"))
    )
    (net (code "69") (name "unconnected-(U1-GND-Pad22)") (class "Default")
      (node (ref "U1") (pin "22") (pinfunction "GND_22") (pintype "input+no_connect"))
    )
    (net (code "70") (name "unconnected-(U1-NRST-Pad24)") (class "Default")
      (node (ref "U1") (pin "24") (pinfunction "NRST_24") (pintype "input+no_connect"))
    )
    (net (code "71") (name "unconnected-(U1-PB0-Pad28)") (class "Default")
      (node (ref "U1") (pin "28") (pinfunction "PB0_28") (pintype "bidirectional+no_connect"))
    )
    (net (code "72") (name "unconnected-(U1-PB1-Pad27)") (class "Default")
      (node (ref "U1") (pin "27") (pinfunction "PB1_27") (pintype "bidirectional+no_connect"))
    )
    (net (code "73") (name "unconnected-(U1-PB3-Pad11)") (class "Default")
      (node (ref "U1") (pin "11") (pinfunction "PB3_11") (pintype "bidirectional+no_connect"))
    )
    (net (code "74") (name "unconnected-(U1-PB4-Pad12)") (class "Default")
      (node (ref "U1") (pin "12") (pinfunction "PB4_12") (pintype "bidirectional+no_connect"))
    )
    (net (code "75") (name "unconnected-(U1-PB5-Pad13)") (class "Default")
      (node (ref "U1") (pin "13") (pinfunction "PB5_13") (pintype "bidirectional+no_connect"))
    )
    (net (code "76") (name "unconnected-(U1-PB8-Pad16)") (class "Default")
      (node (ref "U1") (pin "16") (pinfunction "PB8_16") (pintype "bidirectional+no_connect"))
    )
    (net (code "77") (name "unconnected-(U1-PB9-Pad17)") (class "Default")
      (node (ref "U1") (pin "17") (pinfunction "PB9_17") (pintype "bidirectional+no_connect"))
    )
    (net (code "78") (name "unconnected-(U3-RTS#-Pad4)") (class "Default")
      (node (ref "U3") (pin "4") (pinfunction "RTS#_4") (pintype "unspecified+no_connect"))
    )
    (net (code "79") (name "unconnected-(USB1-SBU1-PadA8)") (class "Default")
      (node (ref "USB1") (pin "A8") (pinfunction "SBU1_A8") (pintype "unspecified+no_connect"))
    )
    (net (code "80") (name "unconnected-(USB1-SBU2-PadB8)") (class "Default")
      (node (ref "USB1") (pin "B8") (pinfunction "SBU2_B8") (pintype "unspecified+no_connect"))
    )
    (net (code "81") (name "unconnected-(USB5-D+-Pad3)") (class "Default")
      (node (ref "USB5") (pin "3") (pinfunction "D+_3") (pintype "input"))
    )
    (net (code "82") (name "unconnected-(USB5-D--Pad2)") (class "Default")
      (node (ref "USB5") (pin "2") (pinfunction "D-_2") (pintype "input"))
    )
    (net (code "83") (name "unconnected-(USB6-D+-Pad3)") (class "Default")
      (node (ref "USB6") (pin "3") (pinfunction "D+_3") (pintype "input"))
    )
    (net (code "84") (name "unconnected-(USB6-D--Pad2)") (class "Default")
      (node (ref "USB6") (pin "2") (pinfunction "D-_2") (pintype "input"))
    )
  )
)
